# SD_TF-CARD.net
KiCad netlist of a schematic drawn in Altium Designer
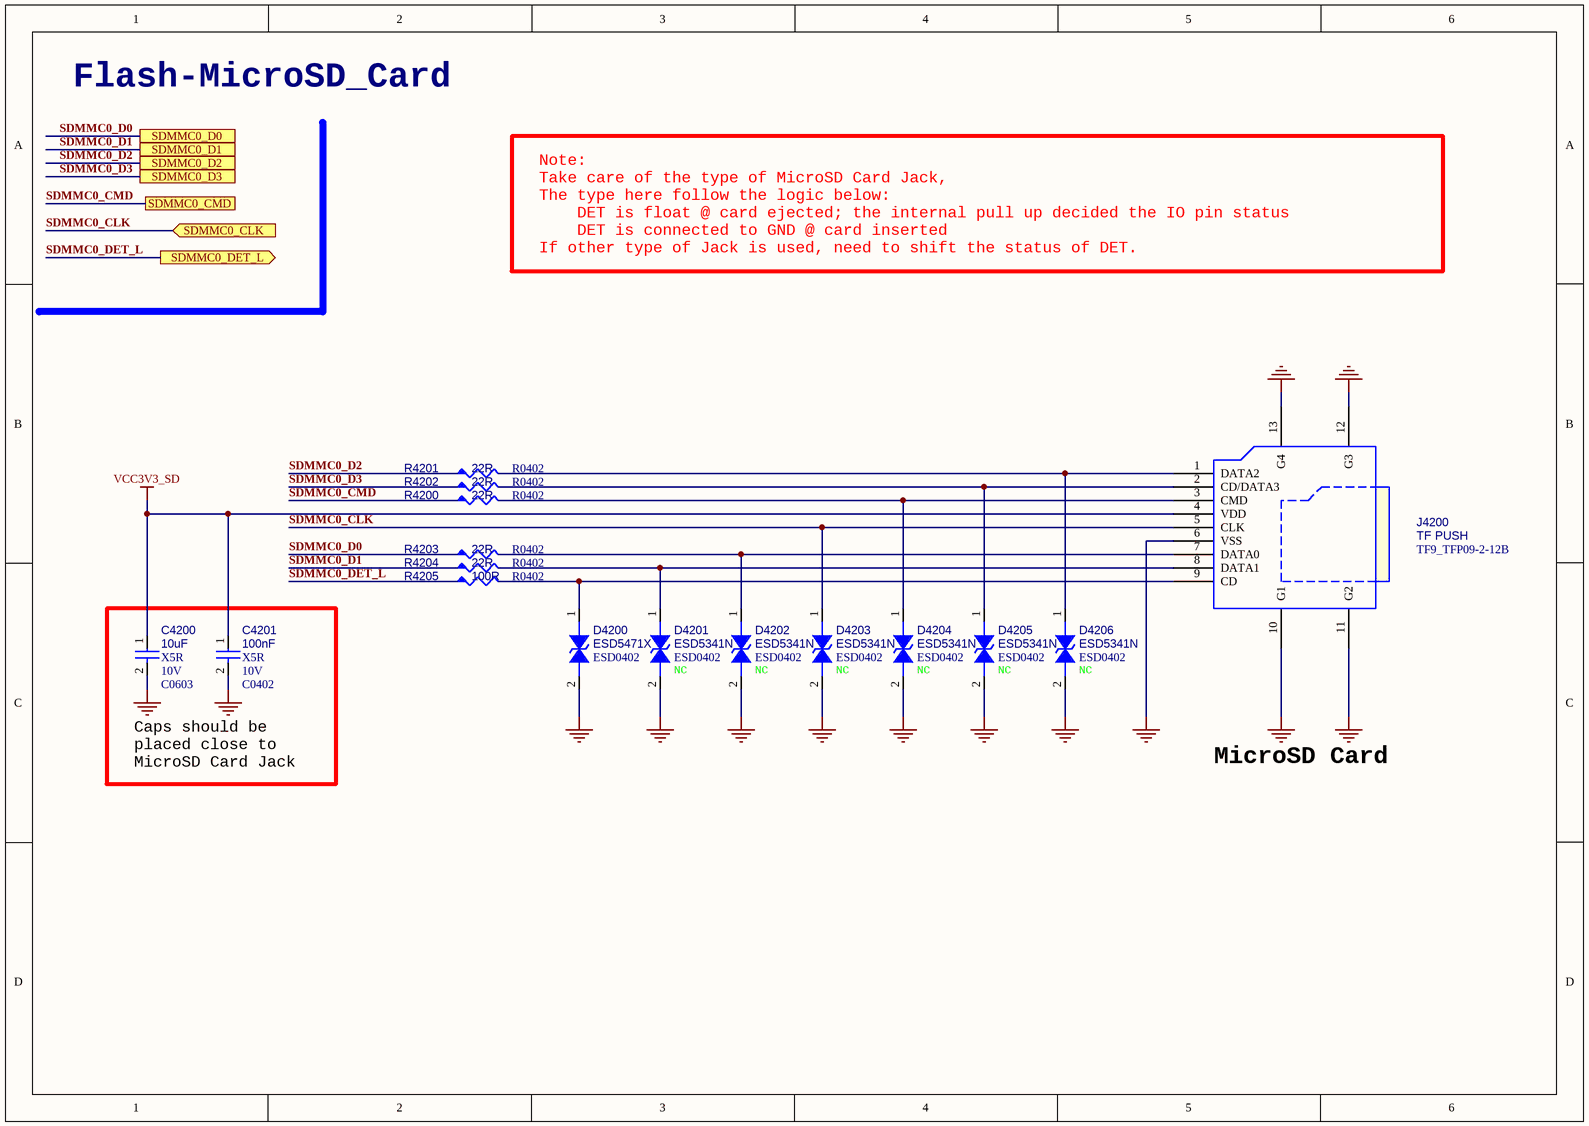
[diagram p0: SD_TF-CARD.SchDoc]

(export (version "E")
  (design (tool "Eeschema 10.0.6"))
  (components
    (comp (ref "C4200")
      (value "10uF")
      (footprint "C0603")
      (description "cap,10.00uF,+/-10%,10V,X5R,C0603")
      (fields
        (field (name "DIELECTRIC") "X5R")
        (field (name "PCB FOOTPRINT") "C0603")
        (field (name "VOLTAGE") "10V")
        (field (name "MANUFACTURER") "TDK")
        (field (name "TOLERANCE") "10%")
        (field (name "CREATED BY") "JJJ")
      )
      (libsource (lib "RK3562_REF") (part "CAP NP"))
    )
    (comp (ref "C4201")
      (value "100nF")
      (footprint "C0402")
      (description "cap,100.00nF,+/-10%,10V,X5R,C0402")
      (fields
        (field (name "DIELECTRIC") "X5R")
        (field (name "PCB FOOTPRINT") "C0402")
        (field (name "VOLTAGE") "10V")
        (field (name "TOLERANCE") "10%")
        (field (name "MANUFACTURER") "TDK")
        (field (name "CREATED BY") "JJJ")
      )
      (libsource (lib "RK3562_REF") (part "CAP NP"))
    )
    (comp (ref "D4200")
      (value "ESD5471X")
      (footprint "ESD0402")
      (description "1-Line, Bi-directional, Transient Voltage Suppressors.9pF.")
      (fields
        (field (name "PCB FOOTPRINT") "ESD0402")
        (field (name "MANUFACTURER") "WillSemi(韦尔半导体)")
        (field (name "CREATED BY") "JJJ")
      )
      (libsource (lib "RK3562_REF") (part "DIODE BI_DIR TRIG"))
    )
    (comp (ref "D4201")
      (value "ESD5341N")
      (footprint "ESD0402")
      (description "1-Line, Bi-directional, Transient Voltage Suppressors.1pF.")
      (fields
        (field (name "PCB FOOTPRINT") "ESD0402")
        (field (name "MANUFACTURER") "WillSemi(韦尔半导体)")
        (field (name "OPTION") "NC")
        (field (name "CREATED BY") "JJJ")
      )
      (libsource (lib "RK3562_REF") (part "DIODE BI_DIR TRIG"))
    )
    (comp (ref "D4202")
      (value "ESD5341N")
      (footprint "ESD0402")
      (description "1-Line, Bi-directional, Transient Voltage Suppressors.1pF.")
      (fields
        (field (name "PCB FOOTPRINT") "ESD0402")
        (field (name "OPTION") "NC")
        (field (name "MANUFACTURER") "WillSemi(韦尔半导体)")
        (field (name "CREATED BY") "JJJ")
      )
      (libsource (lib "RK3562_REF") (part "DIODE BI_DIR TRIG"))
    )
    (comp (ref "D4203")
      (value "ESD5341N")
      (footprint "ESD0402")
      (description "1-Line, Bi-directional, Transient Voltage Suppressors.1pF.")
      (fields
        (field (name "PCB FOOTPRINT") "ESD0402")
        (field (name "OPTION") "NC")
        (field (name "MANUFACTURER") "WillSemi(韦尔半导体)")
        (field (name "CREATED BY") "JJJ")
      )
      (libsource (lib "RK3562_REF") (part "DIODE BI_DIR TRIG"))
    )
    (comp (ref "D4204")
      (value "ESD5341N")
      (footprint "ESD0402")
      (description "1-Line, Bi-directional, Transient Voltage Suppressors.1pF.")
      (fields
        (field (name "PCB FOOTPRINT") "ESD0402")
        (field (name "OPTION") "NC")
        (field (name "MANUFACTURER") "WillSemi(韦尔半导体)")
        (field (name "CREATED BY") "JJJ")
      )
      (libsource (lib "RK3562_REF") (part "DIODE BI_DIR TRIG"))
    )
    (comp (ref "D4205")
      (value "ESD5341N")
      (footprint "ESD0402")
      (description "1-Line, Bi-directional, Transient Voltage Suppressors.1pF.")
      (fields
        (field (name "PCB FOOTPRINT") "ESD0402")
        (field (name "OPTION") "NC")
        (field (name "MANUFACTURER") "WillSemi(韦尔半导体)")
        (field (name "CREATED BY") "JJJ")
      )
      (libsource (lib "RK3562_REF") (part "DIODE BI_DIR TRIG"))
    )
    (comp (ref "D4206")
      (value "ESD5341N")
      (footprint "ESD0402")
      (description "1-Line, Bi-directional, Transient Voltage Suppressors.1pF.")
      (fields
        (field (name "PCB FOOTPRINT") "ESD0402")
        (field (name "OPTION") "NC")
        (field (name "MANUFACTURER") "WillSemi(韦尔半导体)")
        (field (name "CREATED BY") "JJJ")
      )
      (libsource (lib "RK3562_REF") (part "DIODE BI_DIR TRIG"))
    )
    (comp (ref "J4200")
      (value "TF PUSH")
      (footprint "TF-SMD_TF-PUSH")
      (description "通用TF卡座，全尺寸")
      (fields
        (field (name "MANUFACTURER") "旺科达")
        (field (name "MANUFACTURER PART NUMBER") "TFP09-2-12B")
        (field (name "PCB FOOTPRINT") "TF9_TFP09-2-12B")
        (field (name "CREATED BY") "JJJ")
      )
      (libsource (lib "RK3562_REF") (part "TFCARD_SOCKET"))
    )
    (comp (ref "R4200")
      (value "22R")
      (footprint "R0402")
      (description "通用厚膜电阻,22R,+/-5%,R0402,1/16W.")
      (fields
        (field (name "TOLERANCE") "5%")
        (field (name "PCB FOOTPRINT") "R0402")
        (field (name "MANUFACTURER") "YAGEO")
        (field (name "CREATED BY") "YTL")
      )
      (libsource (lib "RK3562_REF") (part "RESISTOR5"))
    )
    (comp (ref "R4201")
      (value "22R")
      (footprint "R0402")
      (description "通用厚膜电阻,22R,+/-5%,R0402,1/16W.")
      (fields
        (field (name "TOLERANCE") "5%")
        (field (name "PCB FOOTPRINT") "R0402")
        (field (name "MANUFACTURER") "YAGEO")
        (field (name "CREATED BY") "YTL")
      )
      (libsource (lib "RK3562_REF") (part "RESISTOR5"))
    )
    (comp (ref "R4202")
      (value "22R")
      (footprint "R0402")
      (description "通用厚膜电阻,22R,+/-5%,R0402,1/16W.")
      (fields
        (field (name "TOLERANCE") "5%")
        (field (name "PCB FOOTPRINT") "R0402")
        (field (name "MANUFACTURER") "YAGEO")
        (field (name "CREATED BY") "YTL")
      )
      (libsource (lib "RK3562_REF") (part "RESISTOR5"))
    )
    (comp (ref "R4203")
      (value "22R")
      (footprint "R0402")
      (description "通用厚膜电阻,22R,+/-5%,R0402,1/16W.")
      (fields
        (field (name "TOLERANCE") "5%")
        (field (name "PCB FOOTPRINT") "R0402")
        (field (name "MANUFACTURER") "YAGEO")
        (field (name "CREATED BY") "YTL")
      )
      (libsource (lib "RK3562_REF") (part "RESISTOR5"))
    )
    (comp (ref "R4204")
      (value "22R")
      (footprint "R0402")
      (description "通用厚膜电阻,22R,+/-5%,R0402,1/16W.")
      (fields
        (field (name "TOLERANCE") "5%")
        (field (name "PCB FOOTPRINT") "R0402")
        (field (name "MANUFACTURER") "YAGEO")
        (field (name "CREATED BY") "YTL")
      )
      (libsource (lib "RK3562_REF") (part "RESISTOR5"))
    )
    (comp (ref "R4205")
      (value "100R")
      (footprint "R0402")
      (description "通用厚膜电阻,100R,+/-5%,R0402,1/16W.")
      (fields
        (field (name "TOLERANCE") "5%")
        (field (name "PCB FOOTPRINT") "R0402")
        (field (name "MANUFACTURER") "YAGEO")
        (field (name "CREATED BY") "YTL")
      )
      (libsource (lib "RK3562_REF") (part "RESISTOR5"))
    )
  )
  (nets
    (net (code "1") (name "/SDMMC0_CLK") (class "Default")
      (node (ref "D4203") (pin "1") (pinfunction "1_1") (pintype "passive"))
      (node (ref "J4200") (pin "5") (pinfunction "CLK_5") (pintype "passive"))
    )
    (net (code "2") (name "/SDMMC0_CMD") (class "Default")
      (node (ref "R4200") (pin "1") (pinfunction "1_1") (pintype "passive"))
    )
    (net (code "3") (name "/SDMMC0_D0") (class "Default")
      (node (ref "R4203") (pin "1") (pinfunction "1_1") (pintype "passive"))
    )
    (net (code "4") (name "/SDMMC0_D1") (class "Default")
      (node (ref "R4204") (pin "1") (pinfunction "1_1") (pintype "passive"))
    )
    (net (code "5") (name "/SDMMC0_D2") (class "Default")
      (node (ref "R4201") (pin "1") (pinfunction "1_1") (pintype "passive"))
    )
    (net (code "6") (name "/SDMMC0_D3") (class "Default")
      (node (ref "R4202") (pin "1") (pinfunction "1_1") (pintype "passive"))
    )
    (net (code "7") (name "/SDMMC0_DET_L") (class "Default")
      (node (ref "R4205") (pin "1") (pinfunction "1_1") (pintype "passive"))
    )
    (net (code "8") (name "GND") (class "Default")
      (node (ref "C4200") (pin "2") (pinfunction "2_2") (pintype "passive"))
      (node (ref "C4201") (pin "2") (pinfunction "2_2") (pintype "passive"))
      (node (ref "D4200") (pin "2") (pinfunction "2_2") (pintype "passive"))
      (node (ref "D4201") (pin "2") (pinfunction "2_2") (pintype "passive"))
      (node (ref "D4202") (pin "2") (pinfunction "2_2") (pintype "passive"))
      (node (ref "D4203") (pin "2") (pinfunction "2_2") (pintype "passive"))
      (node (ref "D4204") (pin "2") (pinfunction "2_2") (pintype "passive"))
      (node (ref "D4205") (pin "2") (pinfunction "2_2") (pintype "passive"))
      (node (ref "D4206") (pin "2") (pinfunction "2_2") (pintype "passive"))
      (node (ref "J4200") (pin "10") (pinfunction "G1_10") (pintype "passive"))
      (node (ref "J4200") (pin "11") (pinfunction "G2_11") (pintype "passive"))
      (node (ref "J4200") (pin "12") (pinfunction "G3_12") (pintype "passive"))
      (node (ref "J4200") (pin "13") (pinfunction "G4_13") (pintype "passive"))
      (node (ref "J4200") (pin "6") (pinfunction "VSS_6") (pintype "passive"))
    )
    (net (code "9") (name "Net-(J4200-CD)") (class "Default")
      (node (ref "D4200") (pin "1") (pinfunction "1_1") (pintype "passive"))
      (node (ref "J4200") (pin "9") (pinfunction "CD_9") (pintype "passive"))
      (node (ref "R4205") (pin "2") (pinfunction "2_2") (pintype "passive"))
    )
    (net (code "10") (name "Net-(J4200-CD{slash}DATA3)") (class "Default")
      (node (ref "D4205") (pin "1") (pinfunction "1_1") (pintype "passive"))
      (node (ref "J4200") (pin "2") (pinfunction "CD/DATA3_2") (pintype "passive"))
      (node (ref "R4202") (pin "2") (pinfunction "2_2") (pintype "passive"))
    )
    (net (code "11") (name "Net-(J4200-CMD)") (class "Default")
      (node (ref "D4204") (pin "1") (pinfunction "1_1") (pintype "passive"))
      (node (ref "J4200") (pin "3") (pinfunction "CMD_3") (pintype "passive"))
      (node (ref "R4200") (pin "2") (pinfunction "2_2") (pintype "passive"))
    )
    (net (code "12") (name "Net-(J4200-DATA0)") (class "Default")
      (node (ref "D4202") (pin "1") (pinfunction "1_1") (pintype "passive"))
      (node (ref "J4200") (pin "7") (pinfunction "DATA0_7") (pintype "passive"))
      (node (ref "R4203") (pin "2") (pinfunction "2_2") (pintype "passive"))
    )
    (net (code "13") (name "Net-(J4200-DATA1)") (class "Default")
      (node (ref "D4201") (pin "1") (pinfunction "1_1") (pintype "passive"))
      (node (ref "J4200") (pin "8") (pinfunction "DATA1_8") (pintype "passive"))
      (node (ref "R4204") (pin "2") (pinfunction "2_2") (pintype "passive"))
    )
    (net (code "14") (name "Net-(J4200-DATA2)") (class "Default")
      (node (ref "D4206") (pin "1") (pinfunction "1_1") (pintype "passive"))
      (node (ref "J4200") (pin "1") (pinfunction "DATA2_1") (pintype "passive"))
      (node (ref "R4201") (pin "2") (pinfunction "2_2") (pintype "passive"))
    )
    (net (code "15") (name "VCC3V3_SD") (class "Default")
      (node (ref "C4200") (pin "1") (pinfunction "1_1") (pintype "passive"))
      (node (ref "C4201") (pin "1") (pinfunction "1_1") (pintype "passive"))
      (node (ref "J4200") (pin "4") (pinfunction "VDD_4") (pintype "passive"))
    )
  )
)
